# CNC-64_IO_PCB_2.net
KiCad netlist of a schematic drawn in EAGLE
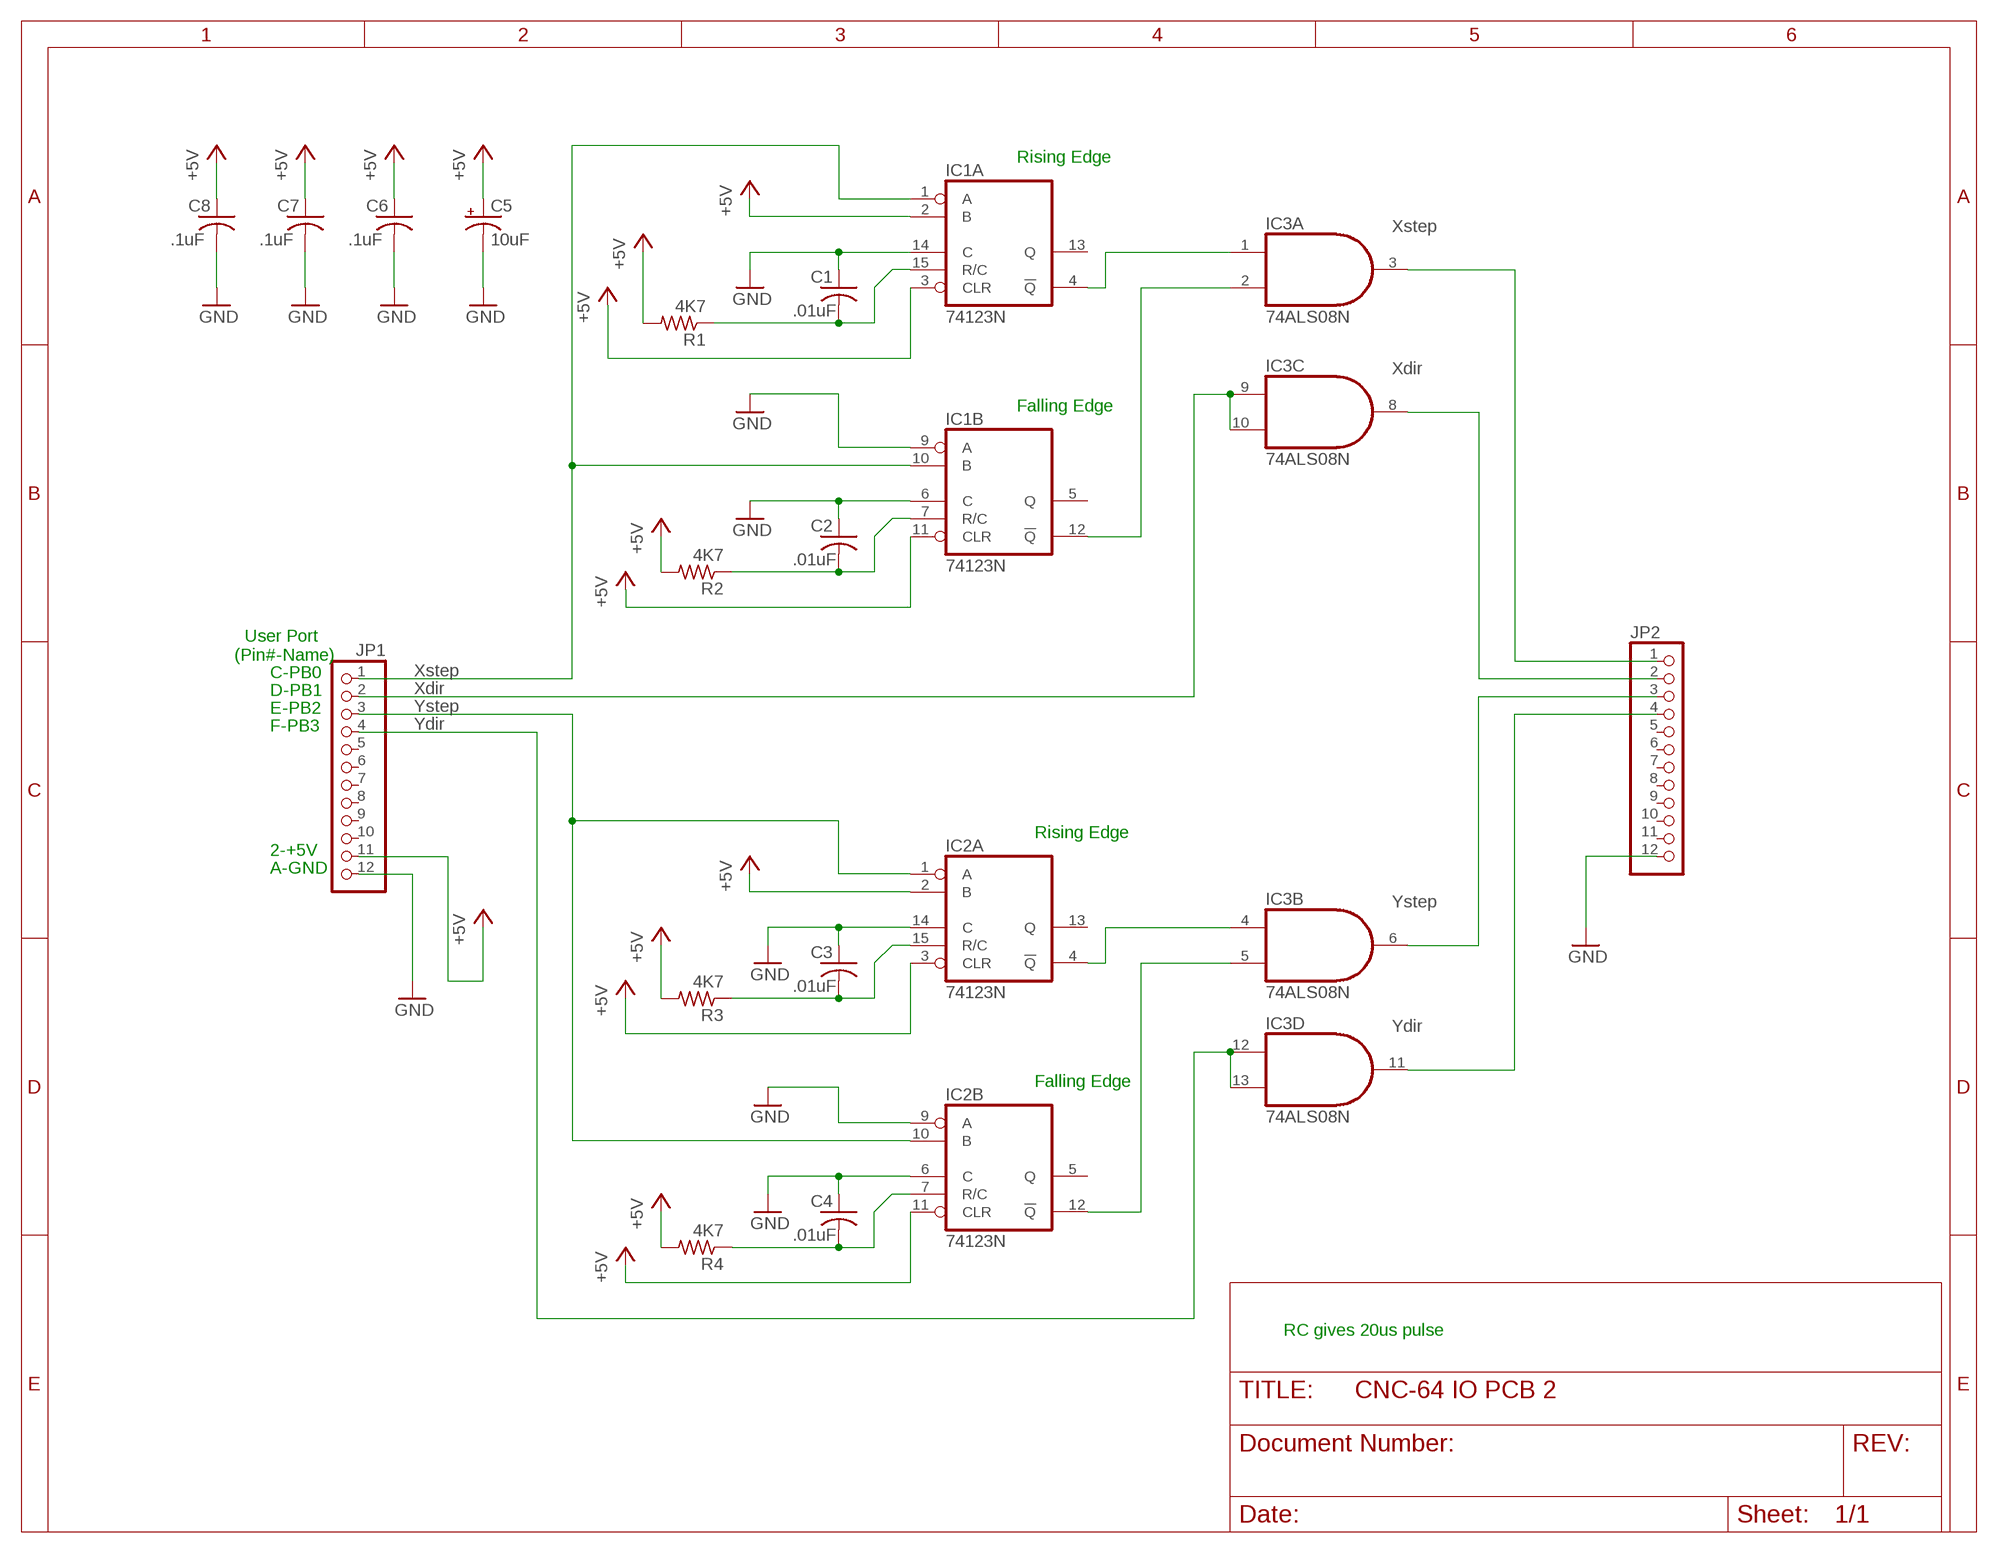
[diagram p0: schematic, sheet 1]

(export (version "E")
  (design (tool "Eeschema 10.0.6"))
  (components
    (comp (ref "C1")
      (value ".01uF")
      (footprint "eagle-import:C050-030X075")
      (libsource (lib "eagle-import") (part "C-US050-030X075"))
    )
    (comp (ref "C2")
      (value ".01uF")
      (footprint "eagle-import:C050-030X075")
      (libsource (lib "eagle-import") (part "C-US050-030X075"))
    )
    (comp (ref "C3")
      (value ".01uF")
      (footprint "eagle-import:C050-030X075")
      (libsource (lib "eagle-import") (part "C-US050-030X075"))
    )
    (comp (ref "C4")
      (value ".01uF")
      (footprint "eagle-import:C050-030X075")
      (libsource (lib "eagle-import") (part "C-US050-030X075"))
    )
    (comp (ref "C5")
      (value "10uF")
      (footprint "eagle-import:E2,5-5")
      (libsource (lib "eagle-import") (part "CPOL-USE2.5-5"))
    )
    (comp (ref "C6")
      (value ".1uF")
      (footprint "eagle-import:C050-030X075")
      (libsource (lib "eagle-import") (part "C-US050-030X075"))
    )
    (comp (ref "C7")
      (value ".1uF")
      (footprint "eagle-import:C050-030X075")
      (libsource (lib "eagle-import") (part "C-US050-030X075"))
    )
    (comp (ref "C8")
      (value ".1uF")
      (footprint "eagle-import:C050-030X075")
      (libsource (lib "eagle-import") (part "C-US050-030X075"))
    )
    (comp (ref "IC1")
      (value "74123N")
      (footprint "eagle-import:DIL16")
      (libsource (lib "eagle-import") (part "74123N"))
    )
    (comp (ref "IC2")
      (value "74123N")
      (footprint "eagle-import:DIL16")
      (libsource (lib "eagle-import") (part "74123N"))
    )
    (comp (ref "IC3")
      (value "74ALS08N")
      (footprint "eagle-import:DIL14")
      (libsource (lib "eagle-import") (part "7408NALS"))
    )
    (comp (ref "JP1")
      (value "PINHD-1X12")
      (footprint "eagle-import:1X12")
      (libsource (lib "eagle-import") (part "PINHD-1X12"))
    )
    (comp (ref "JP2")
      (value "PINHD-1X12")
      (footprint "eagle-import:1X12")
      (libsource (lib "eagle-import") (part "PINHD-1X12"))
    )
    (comp (ref "R1")
      (value "4K7")
      (footprint "eagle-import:0207_10")
      (libsource (lib "eagle-import") (part "R-US_0207/10"))
    )
    (comp (ref "R2")
      (value "4K7")
      (footprint "eagle-import:0207_10")
      (libsource (lib "eagle-import") (part "R-US_0207/10"))
    )
    (comp (ref "R3")
      (value "4K7")
      (footprint "eagle-import:0207_10")
      (libsource (lib "eagle-import") (part "R-US_0207/10"))
    )
    (comp (ref "R4")
      (value "4K7")
      (footprint "eagle-import:0207_10")
      (libsource (lib "eagle-import") (part "R-US_0207/10"))
    )
  )
  (nets
    (net (code "1") (name "+5V") (class "Default")
      (node (ref "C5") (pin "+") (pinfunction "+_+") (pintype "passive"))
      (node (ref "C6") (pin "1") (pinfunction "1_1") (pintype "passive"))
      (node (ref "C7") (pin "1") (pinfunction "1_1") (pintype "passive"))
      (node (ref "C8") (pin "1") (pinfunction "1_1") (pintype "passive"))
      (node (ref "IC1") (pin "11") (pinfunction "CLR_11") (pintype "input"))
      (node (ref "IC1") (pin "2") (pinfunction "B_2") (pintype "input"))
      (node (ref "IC1") (pin "3") (pinfunction "CLR_3") (pintype "input"))
      (node (ref "IC2") (pin "11") (pinfunction "CLR_11") (pintype "input"))
      (node (ref "IC2") (pin "2") (pinfunction "B_2") (pintype "input"))
      (node (ref "IC2") (pin "3") (pinfunction "CLR_3") (pintype "input"))
      (node (ref "JP1") (pin "11") (pinfunction "11_11") (pintype "passive"))
      (node (ref "R1") (pin "2") (pinfunction "2_2") (pintype "passive"))
      (node (ref "R2") (pin "2") (pinfunction "2_2") (pintype "passive"))
      (node (ref "R3") (pin "2") (pinfunction "2_2") (pintype "passive"))
      (node (ref "R4") (pin "2") (pinfunction "2_2") (pintype "passive"))
    )
    (net (code "2") (name "GND") (class "Default")
      (node (ref "C1") (pin "1") (pinfunction "1_1") (pintype "passive"))
      (node (ref "C2") (pin "1") (pinfunction "1_1") (pintype "passive"))
      (node (ref "C3") (pin "1") (pinfunction "1_1") (pintype "passive"))
      (node (ref "C4") (pin "1") (pinfunction "1_1") (pintype "passive"))
      (node (ref "C5") (pin "-") (pinfunction "-_-") (pintype "passive"))
      (node (ref "C6") (pin "2") (pinfunction "2_2") (pintype "passive"))
      (node (ref "C7") (pin "2") (pinfunction "2_2") (pintype "passive"))
      (node (ref "C8") (pin "2") (pinfunction "2_2") (pintype "passive"))
      (node (ref "IC1") (pin "14") (pinfunction "C_14") (pintype "input"))
      (node (ref "IC1") (pin "6") (pinfunction "C_6") (pintype "input"))
      (node (ref "IC1") (pin "9") (pinfunction "A_9") (pintype "input"))
      (node (ref "IC2") (pin "14") (pinfunction "C_14") (pintype "input"))
      (node (ref "IC2") (pin "6") (pinfunction "C_6") (pintype "input"))
      (node (ref "IC2") (pin "9") (pinfunction "A_9") (pintype "input"))
      (node (ref "JP1") (pin "12") (pinfunction "12_12") (pintype "passive"))
      (node (ref "JP2") (pin "12") (pinfunction "12_12") (pintype "passive"))
    )
    (net (code "3") (name "Net-(IC1A-A)") (class "Default")
      (node (ref "IC1") (pin "1") (pinfunction "A_1") (pintype "input"))
      (node (ref "IC1") (pin "10") (pinfunction "B_10") (pintype "input"))
      (node (ref "JP1") (pin "1") (pinfunction "1_1") (pintype "passive"))
    )
    (net (code "4") (name "Net-(IC1A-R{slash}C)") (class "Default")
      (node (ref "C1") (pin "2") (pinfunction "2_2") (pintype "passive"))
      (node (ref "IC1") (pin "15") (pinfunction "R/C_15") (pintype "input"))
      (node (ref "R1") (pin "1") (pinfunction "1_1") (pintype "passive"))
    )
    (net (code "5") (name "Net-(IC1A-~{Q})") (class "Default")
      (node (ref "IC1") (pin "4") (pinfunction "~{Q}_4") (pintype "output"))
      (node (ref "IC3") (pin "1") (pinfunction "I0_1") (pintype "input"))
    )
    (net (code "6") (name "Net-(IC1B-R{slash}C)") (class "Default")
      (node (ref "C2") (pin "2") (pinfunction "2_2") (pintype "passive"))
      (node (ref "IC1") (pin "7") (pinfunction "R/C_7") (pintype "input"))
      (node (ref "R2") (pin "1") (pinfunction "1_1") (pintype "passive"))
    )
    (net (code "7") (name "Net-(IC1B-~{Q})") (class "Default")
      (node (ref "IC1") (pin "12") (pinfunction "~{Q}_12") (pintype "output"))
      (node (ref "IC3") (pin "2") (pinfunction "I1_2") (pintype "input"))
    )
    (net (code "8") (name "Net-(IC2A-A)") (class "Default")
      (node (ref "IC2") (pin "1") (pinfunction "A_1") (pintype "input"))
      (node (ref "IC2") (pin "10") (pinfunction "B_10") (pintype "input"))
      (node (ref "JP1") (pin "3") (pinfunction "3_3") (pintype "passive"))
    )
    (net (code "9") (name "Net-(IC2A-R{slash}C)") (class "Default")
      (node (ref "C3") (pin "2") (pinfunction "2_2") (pintype "passive"))
      (node (ref "IC2") (pin "15") (pinfunction "R/C_15") (pintype "input"))
      (node (ref "R3") (pin "1") (pinfunction "1_1") (pintype "passive"))
    )
    (net (code "10") (name "Net-(IC2A-~{Q})") (class "Default")
      (node (ref "IC2") (pin "4") (pinfunction "~{Q}_4") (pintype "output"))
      (node (ref "IC3") (pin "4") (pinfunction "I0_4") (pintype "input"))
    )
    (net (code "11") (name "Net-(IC2B-R{slash}C)") (class "Default")
      (node (ref "C4") (pin "2") (pinfunction "2_2") (pintype "passive"))
      (node (ref "IC2") (pin "7") (pinfunction "R/C_7") (pintype "input"))
      (node (ref "R4") (pin "1") (pinfunction "1_1") (pintype "passive"))
    )
    (net (code "12") (name "Net-(IC2B-~{Q})") (class "Default")
      (node (ref "IC2") (pin "12") (pinfunction "~{Q}_12") (pintype "output"))
      (node (ref "IC3") (pin "5") (pinfunction "I1_5") (pintype "input"))
    )
    (net (code "13") (name "Net-(IC3A-O)") (class "Default")
      (node (ref "IC3") (pin "3") (pinfunction "O_3") (pintype "output"))
      (node (ref "JP2") (pin "1") (pinfunction "1_1") (pintype "passive"))
    )
    (net (code "14") (name "Net-(IC3B-O)") (class "Default")
      (node (ref "IC3") (pin "6") (pinfunction "O_6") (pintype "output"))
      (node (ref "JP2") (pin "3") (pinfunction "3_3") (pintype "passive"))
    )
    (net (code "15") (name "Net-(IC3C-I0)") (class "Default")
      (node (ref "IC3") (pin "10") (pinfunction "I1_10") (pintype "input"))
      (node (ref "IC3") (pin "9") (pinfunction "I0_9") (pintype "input"))
      (node (ref "JP1") (pin "2") (pinfunction "2_2") (pintype "passive"))
    )
    (net (code "16") (name "Net-(IC3C-O)") (class "Default")
      (node (ref "IC3") (pin "8") (pinfunction "O_8") (pintype "output"))
      (node (ref "JP2") (pin "2") (pinfunction "2_2") (pintype "passive"))
    )
    (net (code "17") (name "Net-(IC3D-I0)") (class "Default")
      (node (ref "IC3") (pin "12") (pinfunction "I0_12") (pintype "input"))
      (node (ref "IC3") (pin "13") (pinfunction "I1_13") (pintype "input"))
      (node (ref "JP1") (pin "4") (pinfunction "4_4") (pintype "passive"))
    )
    (net (code "18") (name "Net-(IC3D-O)") (class "Default")
      (node (ref "IC3") (pin "11") (pinfunction "O_11") (pintype "output"))
      (node (ref "JP2") (pin "4") (pinfunction "4_4") (pintype "passive"))
    )
    (net (code "19") (name "unconnected-(IC1A-Q-Pad13)") (class "Default")
      (node (ref "IC1") (pin "13") (pinfunction "Q_13") (pintype "output"))
    )
    (net (code "20") (name "unconnected-(IC1B-Q-Pad5)") (class "Default")
      (node (ref "IC1") (pin "5") (pinfunction "Q_5") (pintype "output"))
    )
    (net (code "21") (name "unconnected-(IC2A-Q-Pad13)") (class "Default")
      (node (ref "IC2") (pin "13") (pinfunction "Q_13") (pintype "output"))
    )
    (net (code "22") (name "unconnected-(IC2B-Q-Pad5)") (class "Default")
      (node (ref "IC2") (pin "5") (pinfunction "Q_5") (pintype "output"))
    )
    (net (code "23") (name "unconnected-(JP1-Pad5)") (class "Default")
      (node (ref "JP1") (pin "5") (pinfunction "5_5") (pintype "passive"))
    )
    (net (code "24") (name "unconnected-(JP1-Pad6)") (class "Default")
      (node (ref "JP1") (pin "6") (pinfunction "6_6") (pintype "passive"))
    )
    (net (code "25") (name "unconnected-(JP1-Pad7)") (class "Default")
      (node (ref "JP1") (pin "7") (pinfunction "7_7") (pintype "passive"))
    )
    (net (code "26") (name "unconnected-(JP1-Pad8)") (class "Default")
      (node (ref "JP1") (pin "8") (pinfunction "8_8") (pintype "passive"))
    )
    (net (code "27") (name "unconnected-(JP1-Pad9)") (class "Default")
      (node (ref "JP1") (pin "9") (pinfunction "9_9") (pintype "passive"))
    )
    (net (code "28") (name "unconnected-(JP1-Pad10)") (class "Default")
      (node (ref "JP1") (pin "10") (pinfunction "10_10") (pintype "passive"))
    )
    (net (code "29") (name "unconnected-(JP2-Pad5)") (class "Default")
      (node (ref "JP2") (pin "5") (pinfunction "5_5") (pintype "passive"))
    )
    (net (code "30") (name "unconnected-(JP2-Pad6)") (class "Default")
      (node (ref "JP2") (pin "6") (pinfunction "6_6") (pintype "passive"))
    )
    (net (code "31") (name "unconnected-(JP2-Pad7)") (class "Default")
      (node (ref "JP2") (pin "7") (pinfunction "7_7") (pintype "passive"))
    )
    (net (code "32") (name "unconnected-(JP2-Pad8)") (class "Default")
      (node (ref "JP2") (pin "8") (pinfunction "8_8") (pintype "passive"))
    )
    (net (code "33") (name "unconnected-(JP2-Pad9)") (class "Default")
      (node (ref "JP2") (pin "9") (pinfunction "9_9") (pintype "passive"))
    )
    (net (code "34") (name "unconnected-(JP2-Pad10)") (class "Default")
      (node (ref "JP2") (pin "10") (pinfunction "10_10") (pintype "passive"))
    )
    (net (code "35") (name "unconnected-(JP2-Pad11)") (class "Default")
      (node (ref "JP2") (pin "11") (pinfunction "11_11") (pintype "passive"))
    )
  )
)
